# saha-aux.net
KiCad netlist of a schematic drawn in EAGLE
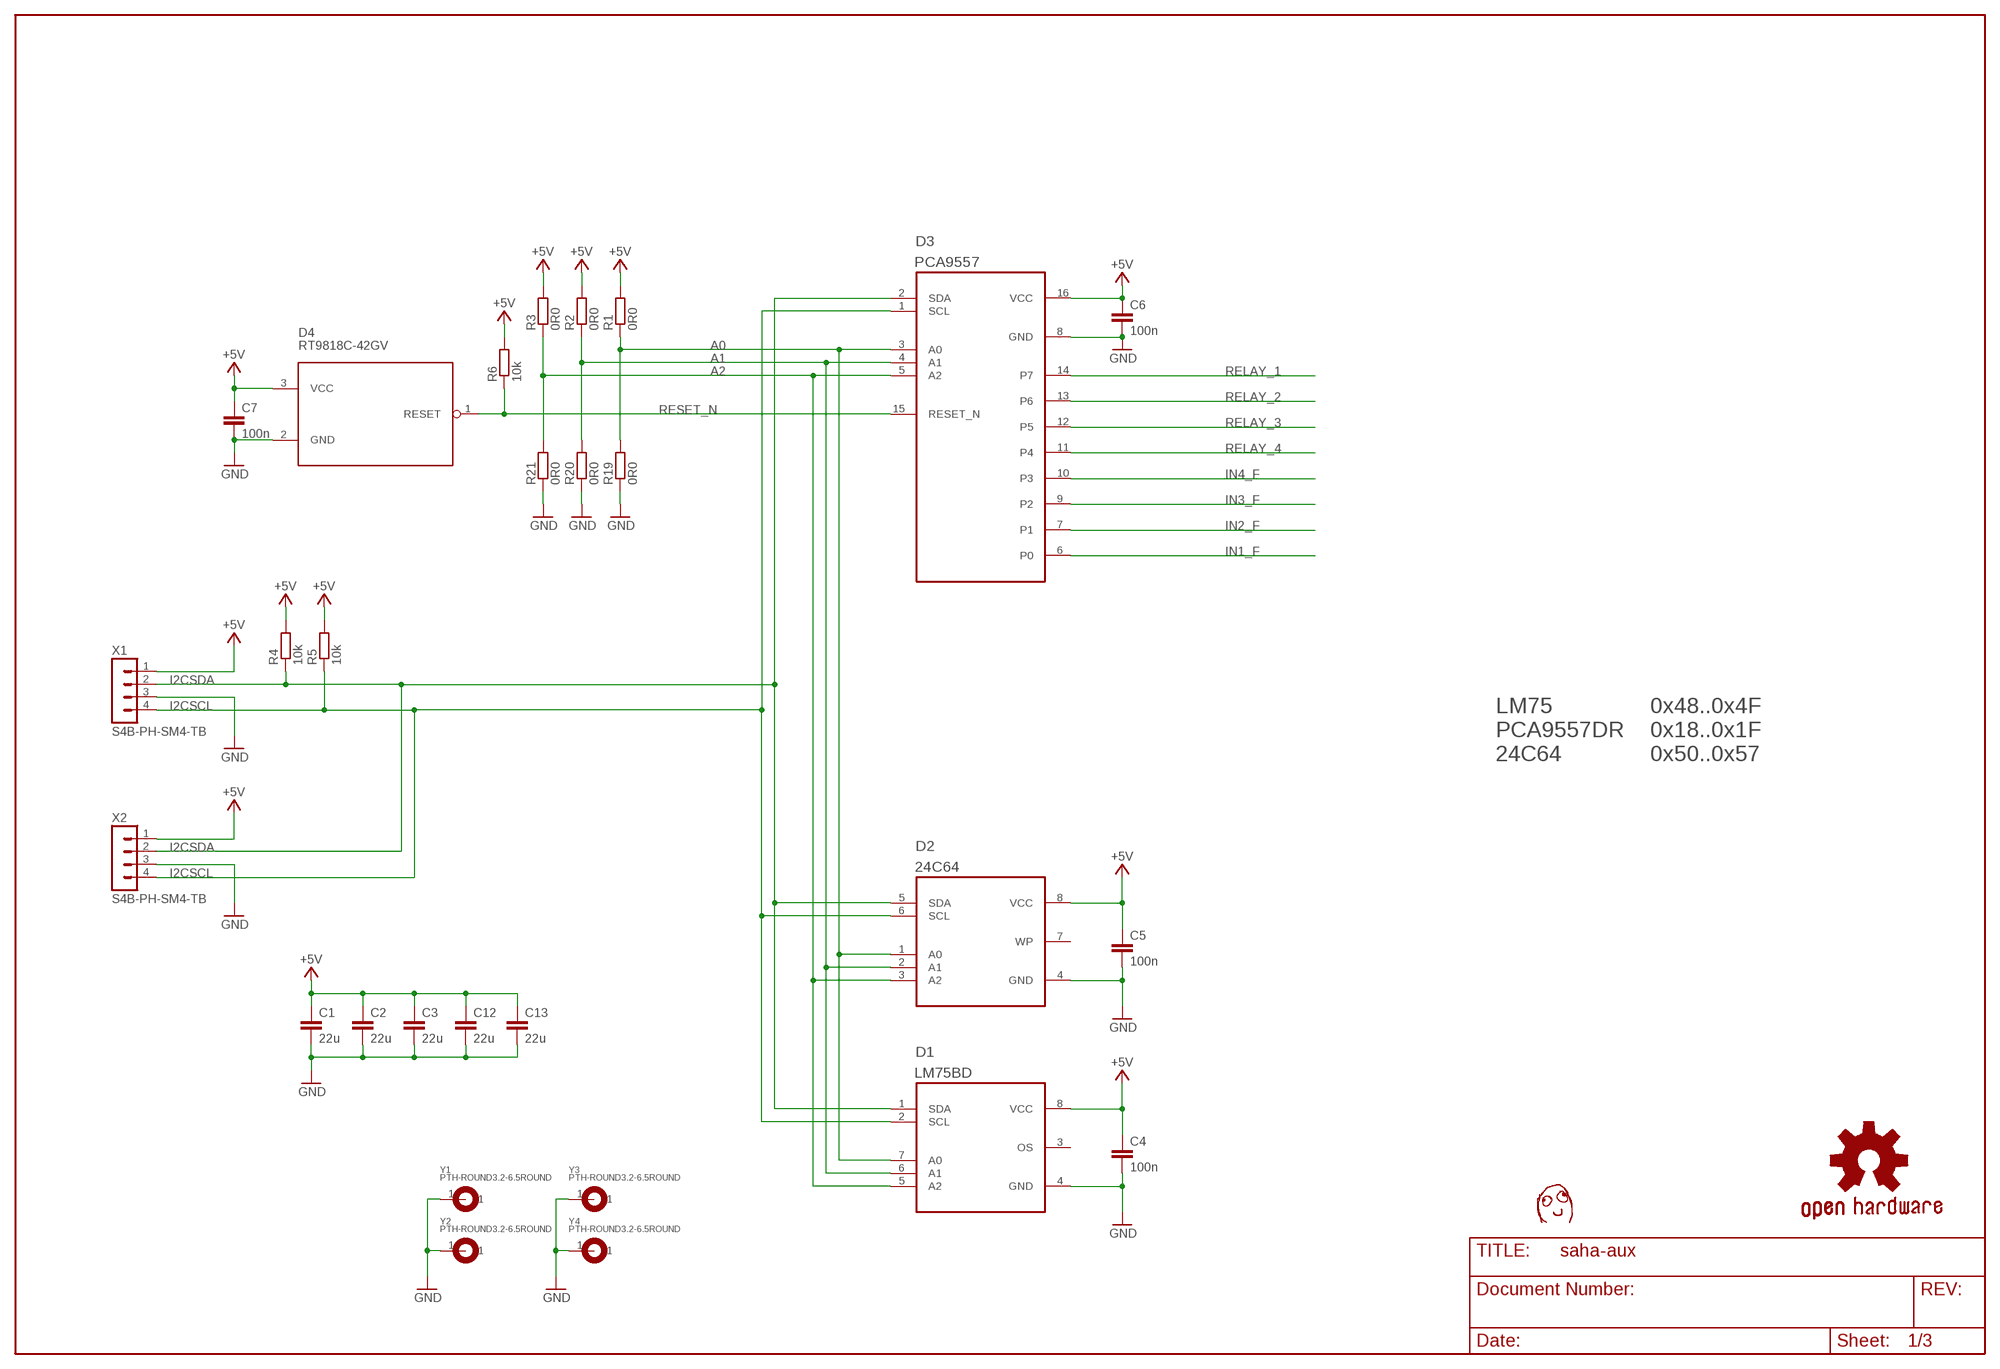
[diagram p0: schematic, sheet 1]
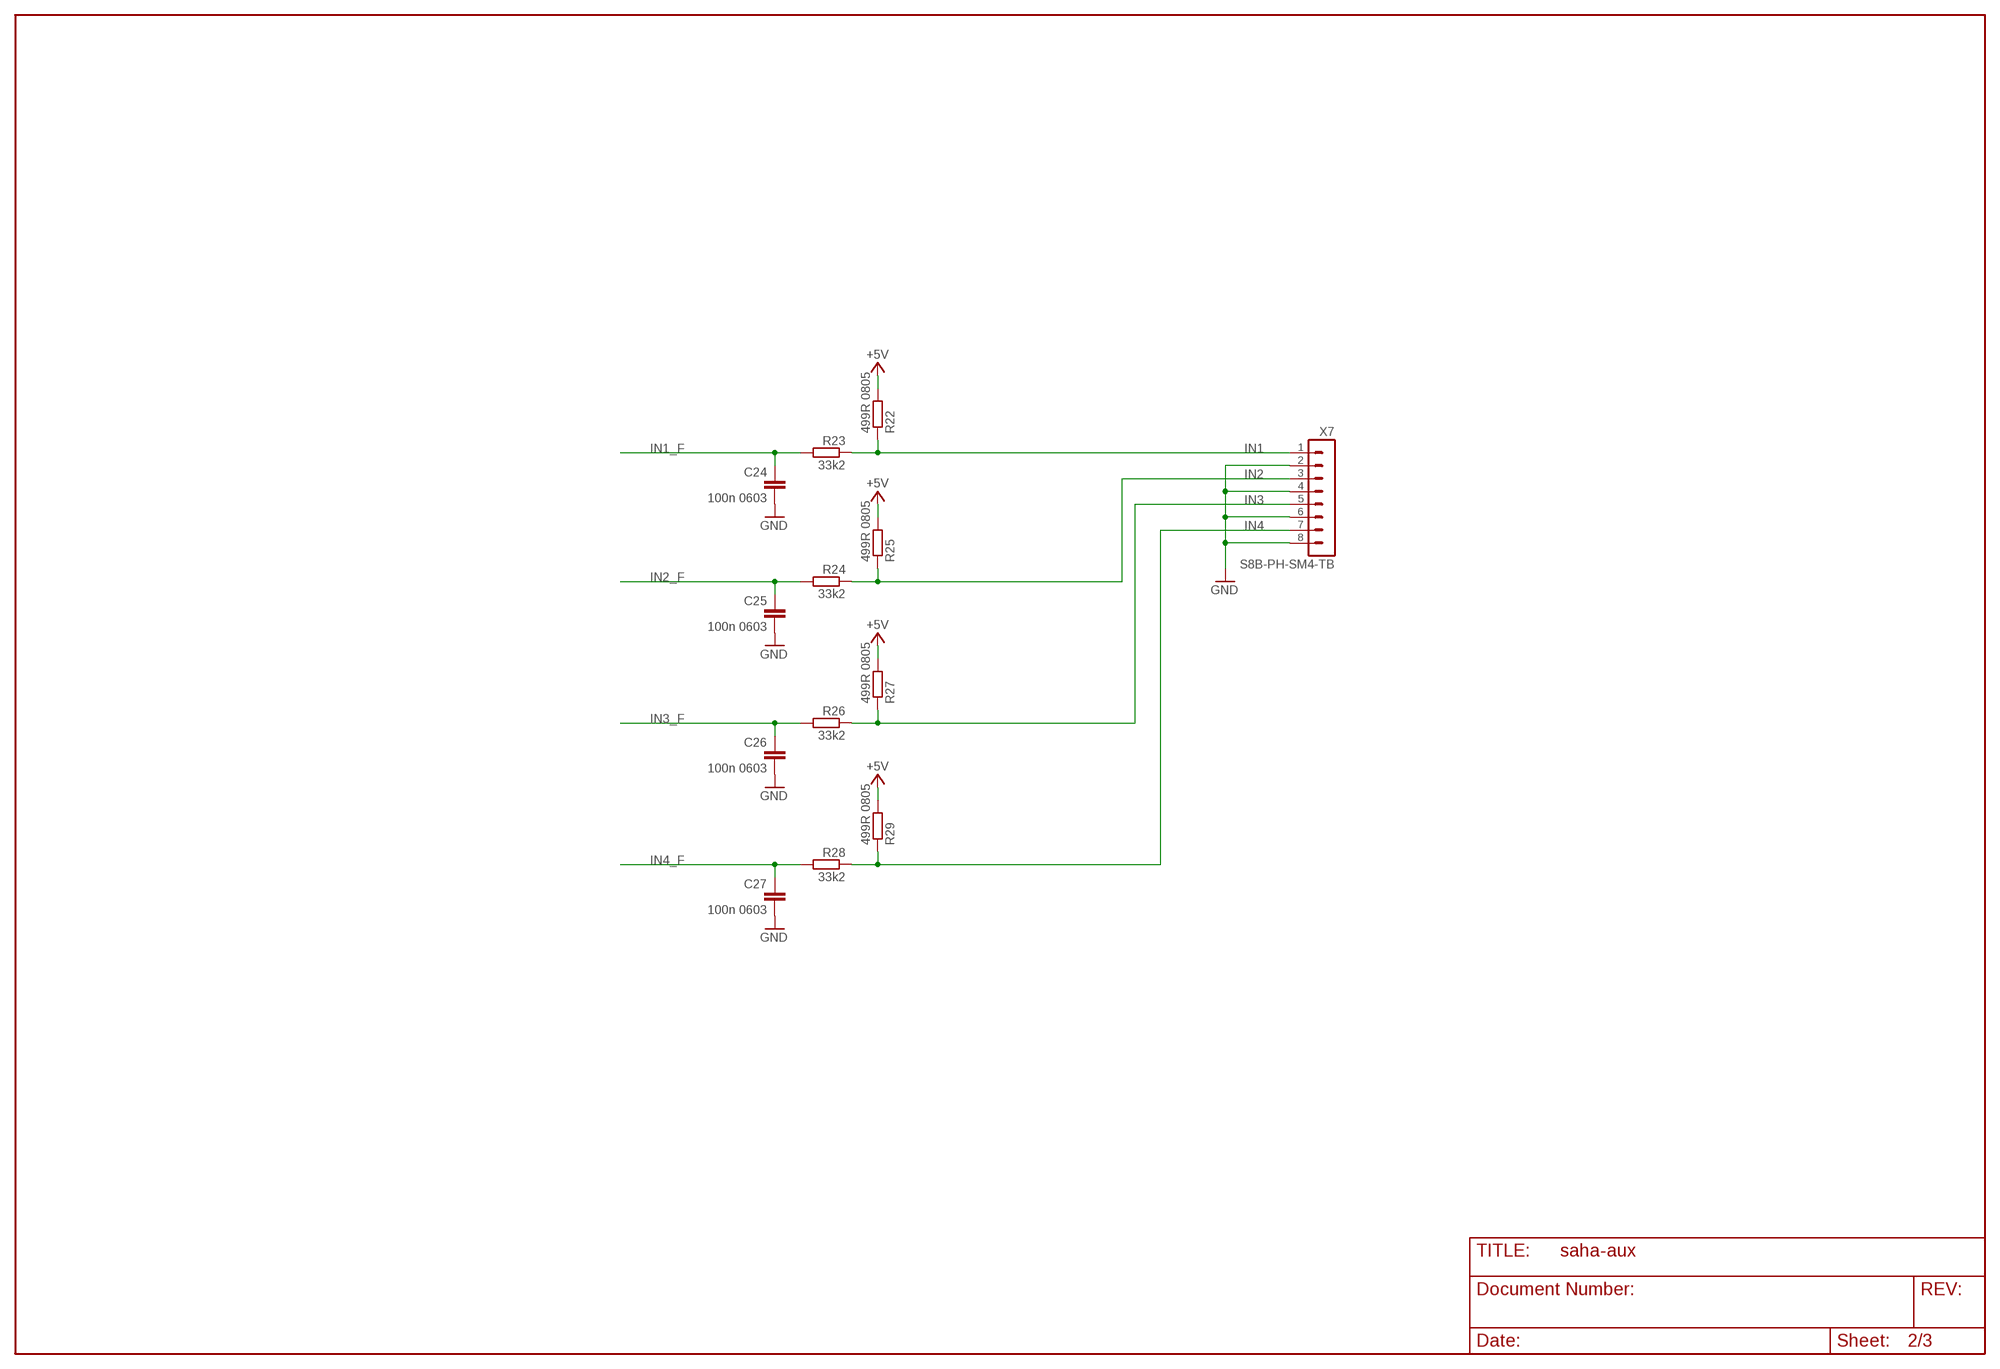
[diagram p1: schematic, sheet 2]
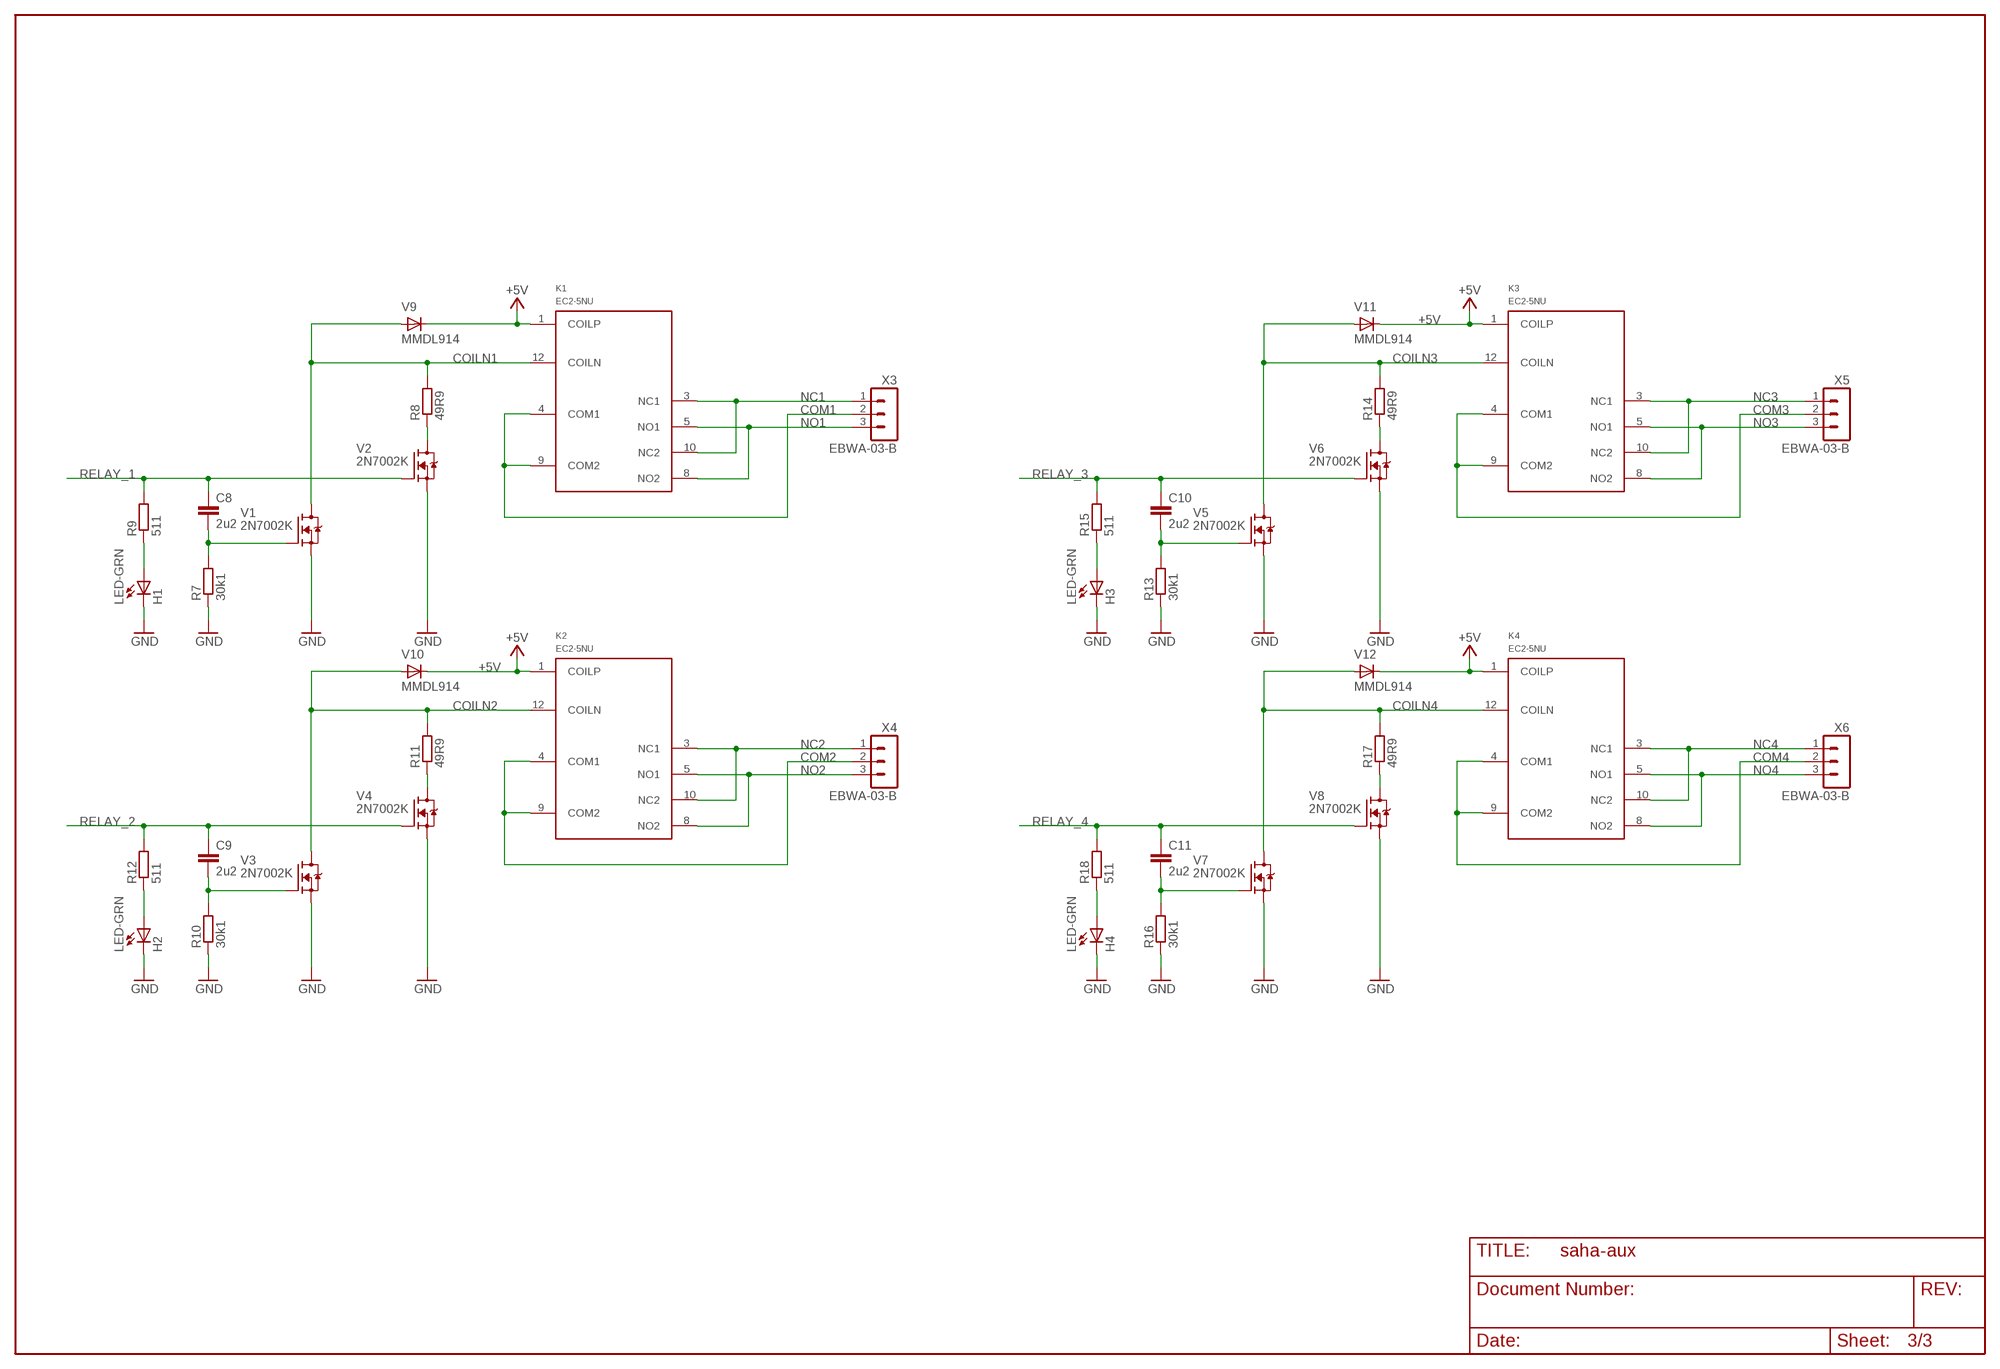
[diagram p2: schematic, sheet 3]

(export (version "E")
  (design (tool "Eeschema 10.0.6"))
  (components
    (comp (ref "C8")
      (value "2u2")
      (footprint "eagle-import:C0603")
      (libsource (lib "eagle-import") (part "CAP0603"))
    )
    (comp (ref "C9")
      (value "2u2")
      (footprint "eagle-import:C0603")
      (libsource (lib "eagle-import") (part "CAP0603"))
    )
    (comp (ref "C10")
      (value "2u2")
      (footprint "eagle-import:C0603")
      (libsource (lib "eagle-import") (part "CAP0603"))
    )
    (comp (ref "C11")
      (value "2u2")
      (footprint "eagle-import:C0603")
      (libsource (lib "eagle-import") (part "CAP0603"))
    )
    (comp (ref "H1")
      (value "LED-GRN")
      (footprint "eagle-import:CHIP-LED0603")
      (libsource (lib "eagle-import") (part "LED-GRN"))
    )
    (comp (ref "H2")
      (value "LED-GRN")
      (footprint "eagle-import:CHIP-LED0603")
      (libsource (lib "eagle-import") (part "LED-GRN"))
    )
    (comp (ref "H3")
      (value "LED-GRN")
      (footprint "eagle-import:CHIP-LED0603")
      (libsource (lib "eagle-import") (part "LED-GRN"))
    )
    (comp (ref "H4")
      (value "LED-GRN")
      (footprint "eagle-import:CHIP-LED0603")
      (libsource (lib "eagle-import") (part "LED-GRN"))
    )
    (comp (ref "K1")
      (value "EC2-5NU")
      (footprint "eagle-import:EC2")
      (libsource (lib "eagle-import") (part "EC2-5NU"))
    )
    (comp (ref "K2")
      (value "EC2-5NU")
      (footprint "eagle-import:EC2")
      (libsource (lib "eagle-import") (part "EC2-5NU"))
    )
    (comp (ref "K3")
      (value "EC2-5NU")
      (footprint "eagle-import:EC2")
      (libsource (lib "eagle-import") (part "EC2-5NU"))
    )
    (comp (ref "K4")
      (value "EC2-5NU")
      (footprint "eagle-import:EC2")
      (libsource (lib "eagle-import") (part "EC2-5NU"))
    )
    (comp (ref "R7")
      (value "30k1")
      (footprint "eagle-import:R0603")
      (libsource (lib "eagle-import") (part "RES0603"))
    )
    (comp (ref "R8")
      (value "49R9")
      (footprint "eagle-import:R0805")
      (libsource (lib "eagle-import") (part "RES0805"))
    )
    (comp (ref "R9")
      (value "511")
      (footprint "eagle-import:R0603")
      (libsource (lib "eagle-import") (part "RES0603"))
    )
    (comp (ref "R10")
      (value "30k1")
      (footprint "eagle-import:R0603")
      (libsource (lib "eagle-import") (part "RES0603"))
    )
    (comp (ref "R11")
      (value "49R9")
      (footprint "eagle-import:R0805")
      (libsource (lib "eagle-import") (part "RES0805"))
    )
    (comp (ref "R12")
      (value "511")
      (footprint "eagle-import:R0603")
      (libsource (lib "eagle-import") (part "RES0603"))
    )
    (comp (ref "R13")
      (value "30k1")
      (footprint "eagle-import:R0603")
      (libsource (lib "eagle-import") (part "RES0603"))
    )
    (comp (ref "R14")
      (value "49R9")
      (footprint "eagle-import:R0805")
      (libsource (lib "eagle-import") (part "RES0805"))
    )
    (comp (ref "R15")
      (value "511")
      (footprint "eagle-import:R0603")
      (libsource (lib "eagle-import") (part "RES0603"))
    )
    (comp (ref "R16")
      (value "30k1")
      (footprint "eagle-import:R0603")
      (libsource (lib "eagle-import") (part "RES0603"))
    )
    (comp (ref "R17")
      (value "49R9")
      (footprint "eagle-import:R0805")
      (libsource (lib "eagle-import") (part "RES0805"))
    )
    (comp (ref "R18")
      (value "511")
      (footprint "eagle-import:R0603")
      (libsource (lib "eagle-import") (part "RES0603"))
    )
    (comp (ref "V1")
      (value "2N7002K")
      (footprint "eagle-import:SOT23")
      (libsource (lib "eagle-import") (part "2N7002K"))
    )
    (comp (ref "V2")
      (value "2N7002K")
      (footprint "eagle-import:SOT23")
      (libsource (lib "eagle-import") (part "2N7002K"))
    )
    (comp (ref "V3")
      (value "2N7002K")
      (footprint "eagle-import:SOT23")
      (libsource (lib "eagle-import") (part "2N7002K"))
    )
    (comp (ref "V4")
      (value "2N7002K")
      (footprint "eagle-import:SOT23")
      (libsource (lib "eagle-import") (part "2N7002K"))
    )
    (comp (ref "V5")
      (value "2N7002K")
      (footprint "eagle-import:SOT23")
      (libsource (lib "eagle-import") (part "2N7002K"))
    )
    (comp (ref "V6")
      (value "2N7002K")
      (footprint "eagle-import:SOT23")
      (libsource (lib "eagle-import") (part "2N7002K"))
    )
    (comp (ref "V7")
      (value "2N7002K")
      (footprint "eagle-import:SOT23")
      (libsource (lib "eagle-import") (part "2N7002K"))
    )
    (comp (ref "V8")
      (value "2N7002K")
      (footprint "eagle-import:SOT23")
      (libsource (lib "eagle-import") (part "2N7002K"))
    )
    (comp (ref "V9")
      (value "MMDL914")
      (footprint "eagle-import:SOD-323")
      (libsource (lib "eagle-import") (part "MMDL914"))
    )
    (comp (ref "V10")
      (value "MMDL914")
      (footprint "eagle-import:SOD-323")
      (libsource (lib "eagle-import") (part "MMDL914"))
    )
    (comp (ref "V11")
      (value "MMDL914")
      (footprint "eagle-import:SOD-323")
      (libsource (lib "eagle-import") (part "MMDL914"))
    )
    (comp (ref "V12")
      (value "MMDL914")
      (footprint "eagle-import:SOD-323")
      (libsource (lib "eagle-import") (part "MMDL914"))
    )
    (comp (ref "X3")
      (value "EBWA-03-B")
      (footprint "eagle-import:RUUVILIITIN381-3")
      (libsource (lib "eagle-import") (part "EBWA-03-B"))
    )
    (comp (ref "X4")
      (value "EBWA-03-B")
      (footprint "eagle-import:RUUVILIITIN381-3")
      (libsource (lib "eagle-import") (part "EBWA-03-B"))
    )
    (comp (ref "X5")
      (value "EBWA-03-B")
      (footprint "eagle-import:RUUVILIITIN381-3")
      (libsource (lib "eagle-import") (part "EBWA-03-B"))
    )
    (comp (ref "X6")
      (value "EBWA-03-B")
      (footprint "eagle-import:RUUVILIITIN381-3")
      (libsource (lib "eagle-import") (part "EBWA-03-B"))
    )
    (comp (ref "C1")
      (value "22u")
      (footprint "eagle-import:C0805")
      (libsource (lib "eagle-import") (part "CAP0805"))
    )
    (comp (ref "C2")
      (value "22u")
      (footprint "eagle-import:C0805")
      (libsource (lib "eagle-import") (part "CAP0805"))
    )
    (comp (ref "C3")
      (value "22u")
      (footprint "eagle-import:C0805")
      (libsource (lib "eagle-import") (part "CAP0805"))
    )
    (comp (ref "C4")
      (value "100n")
      (footprint "eagle-import:C0603")
      (libsource (lib "eagle-import") (part "CAP0603"))
    )
    (comp (ref "C5")
      (value "100n")
      (footprint "eagle-import:C0603")
      (libsource (lib "eagle-import") (part "CAP0603"))
    )
    (comp (ref "C6")
      (value "100n")
      (footprint "eagle-import:C0603")
      (libsource (lib "eagle-import") (part "CAP0603"))
    )
    (comp (ref "C7")
      (value "100n")
      (footprint "eagle-import:C0603")
      (libsource (lib "eagle-import") (part "CAP0603"))
    )
    (comp (ref "C12")
      (value "22u")
      (footprint "eagle-import:C0805")
      (libsource (lib "eagle-import") (part "CAP0805"))
    )
    (comp (ref "C13")
      (value "22u")
      (footprint "eagle-import:C0805")
      (libsource (lib "eagle-import") (part "CAP0805"))
    )
    (comp (ref "D1")
      (value "LM75BD")
      (footprint "eagle-import:SOIC8-N")
      (libsource (lib "eagle-import") (part "LM75BD"))
    )
    (comp (ref "D2")
      (value "24C64")
      (footprint "eagle-import:SOIC8-N")
      (libsource (lib "eagle-import") (part "24C64"))
    )
    (comp (ref "D3")
      (value "PCA9557")
      (footprint "eagle-import:SOIC16-N")
      (libsource (lib "eagle-import") (part "PCA9557"))
    )
    (comp (ref "D4")
      (value "RT9818C-42GV")
      (footprint "eagle-import:SOT23")
      (libsource (lib "eagle-import") (part "RT9818C-42GV"))
    )
    (comp (ref "R1")
      (value "0R0")
      (footprint "eagle-import:R0603")
      (libsource (lib "eagle-import") (part "RES0603"))
    )
    (comp (ref "R2")
      (value "0R0")
      (footprint "eagle-import:R0603")
      (libsource (lib "eagle-import") (part "RES0603"))
    )
    (comp (ref "R3")
      (value "0R0")
      (footprint "eagle-import:R0603")
      (libsource (lib "eagle-import") (part "RES0603"))
    )
    (comp (ref "R4")
      (value "10k")
      (footprint "eagle-import:R0603")
      (libsource (lib "eagle-import") (part "RES0603"))
    )
    (comp (ref "R5")
      (value "10k")
      (footprint "eagle-import:R0603")
      (libsource (lib "eagle-import") (part "RES0603"))
    )
    (comp (ref "R6")
      (value "10k")
      (footprint "eagle-import:R0603")
      (libsource (lib "eagle-import") (part "RES0603"))
    )
    (comp (ref "R19")
      (value "0R0")
      (footprint "eagle-import:R0603")
      (libsource (lib "eagle-import") (part "RES0603"))
    )
    (comp (ref "R20")
      (value "0R0")
      (footprint "eagle-import:R0603")
      (libsource (lib "eagle-import") (part "RES0603"))
    )
    (comp (ref "R21")
      (value "0R0")
      (footprint "eagle-import:R0603")
      (libsource (lib "eagle-import") (part "RES0603"))
    )
    (comp (ref "U$1")
      (value "DAFUG")
      (footprint "eagle-import:DAFUG")
      (libsource (lib "eagle-import") (part "DAFUG"))
    )
    (comp (ref "X1")
      (value "S4B-PH-SM4-TB")
      (footprint "eagle-import:JST-PH2.0-RA-4")
      (libsource (lib "eagle-import") (part "S4B-PH-SM4-TB"))
    )
    (comp (ref "X2")
      (value "S4B-PH-SM4-TB")
      (footprint "eagle-import:JST-PH2.0-RA-4")
      (libsource (lib "eagle-import") (part "S4B-PH-SM4-TB"))
    )
    (comp (ref "Y1")
      (value "PTH-ROUND3.2-6.5ROUND")
      (footprint "eagle-import:EKE_PTH-3.2-6.5")
      (libsource (lib "eagle-import") (part "PTH-ROUND3.2-6.5ROUND"))
    )
    (comp (ref "Y2")
      (value "PTH-ROUND3.2-6.5ROUND")
      (footprint "eagle-import:EKE_PTH-3.2-6.5")
      (libsource (lib "eagle-import") (part "PTH-ROUND3.2-6.5ROUND"))
    )
    (comp (ref "Y3")
      (value "PTH-ROUND3.2-6.5ROUND")
      (footprint "eagle-import:EKE_PTH-3.2-6.5")
      (libsource (lib "eagle-import") (part "PTH-ROUND3.2-6.5ROUND"))
    )
    (comp (ref "Y4")
      (value "PTH-ROUND3.2-6.5ROUND")
      (footprint "eagle-import:EKE_PTH-3.2-6.5")
      (libsource (lib "eagle-import") (part "PTH-ROUND3.2-6.5ROUND"))
    )
    (comp (ref "C24")
      (value "100n 0603")
      (footprint "eagle-import:C0603")
      (libsource (lib "eagle-import") (part "saha-cpu_CAP0603"))
    )
    (comp (ref "C25")
      (value "100n 0603")
      (footprint "eagle-import:C0603")
      (libsource (lib "eagle-import") (part "saha-cpu_CAP0603"))
    )
    (comp (ref "C26")
      (value "100n 0603")
      (footprint "eagle-import:C0603")
      (libsource (lib "eagle-import") (part "saha-cpu_CAP0603"))
    )
    (comp (ref "C27")
      (value "100n 0603")
      (footprint "eagle-import:C0603")
      (libsource (lib "eagle-import") (part "saha-cpu_CAP0603"))
    )
    (comp (ref "R22")
      (value "499R 0805")
      (footprint "eagle-import:R0805")
      (libsource (lib "eagle-import") (part "saha-cpu_RES0805"))
    )
    (comp (ref "R23")
      (value "33k2")
      (footprint "eagle-import:R0603")
      (libsource (lib "eagle-import") (part "saha-cpu_RES0603"))
    )
    (comp (ref "R24")
      (value "33k2")
      (footprint "eagle-import:R0603")
      (libsource (lib "eagle-import") (part "saha-cpu_RES0603"))
    )
    (comp (ref "R25")
      (value "499R 0805")
      (footprint "eagle-import:R0805")
      (libsource (lib "eagle-import") (part "saha-cpu_RES0805"))
    )
    (comp (ref "R26")
      (value "33k2")
      (footprint "eagle-import:R0603")
      (libsource (lib "eagle-import") (part "saha-cpu_RES0603"))
    )
    (comp (ref "R27")
      (value "499R 0805")
      (footprint "eagle-import:R0805")
      (libsource (lib "eagle-import") (part "saha-cpu_RES0805"))
    )
    (comp (ref "R28")
      (value "33k2")
      (footprint "eagle-import:R0603")
      (libsource (lib "eagle-import") (part "saha-cpu_RES0603"))
    )
    (comp (ref "R29")
      (value "499R 0805")
      (footprint "eagle-import:R0805")
      (libsource (lib "eagle-import") (part "saha-cpu_RES0805"))
    )
    (comp (ref "X7")
      (value "S8B-PH-SM4-TB")
      (footprint "eagle-import:JST-PH2.0-RA-8")
      (libsource (lib "eagle-import") (part "S8B-PH-SM4-TB"))
    )
  )
  (nets
    (net (code "1") (name "+5V") (class "Default")
      (node (ref "C1") (pin "1") (pinfunction "1_1") (pintype "passive"))
      (node (ref "C12") (pin "1") (pinfunction "1_1") (pintype "passive"))
      (node (ref "C13") (pin "1") (pinfunction "1_1") (pintype "passive"))
      (node (ref "C2") (pin "1") (pinfunction "1_1") (pintype "passive"))
      (node (ref "C3") (pin "1") (pinfunction "1_1") (pintype "passive"))
      (node (ref "C4") (pin "1") (pinfunction "1_1") (pintype "passive"))
      (node (ref "C5") (pin "1") (pinfunction "1_1") (pintype "passive"))
      (node (ref "C6") (pin "1") (pinfunction "1_1") (pintype "passive"))
      (node (ref "C7") (pin "1") (pinfunction "1_1") (pintype "passive"))
      (node (ref "D1") (pin "8") (pinfunction "VCC_8") (pintype "bidirectional"))
      (node (ref "D2") (pin "8") (pinfunction "VCC_8") (pintype "bidirectional"))
      (node (ref "D3") (pin "16") (pinfunction "VCC_16") (pintype "bidirectional"))
      (node (ref "D4") (pin "3") (pinfunction "VCC_3") (pintype "bidirectional"))
      (node (ref "K1") (pin "1") (pinfunction "COILP_1") (pintype "bidirectional"))
      (node (ref "K2") (pin "1") (pinfunction "COILP_1") (pintype "bidirectional"))
      (node (ref "K3") (pin "1") (pinfunction "COILP_1") (pintype "bidirectional"))
      (node (ref "K4") (pin "1") (pinfunction "COILP_1") (pintype "bidirectional"))
      (node (ref "R1") (pin "2") (pinfunction "2_2") (pintype "passive"))
      (node (ref "R2") (pin "2") (pinfunction "2_2") (pintype "passive"))
      (node (ref "R22") (pin "2") (pinfunction "2_2") (pintype "passive"))
      (node (ref "R25") (pin "2") (pinfunction "2_2") (pintype "passive"))
      (node (ref "R27") (pin "2") (pinfunction "2_2") (pintype "passive"))
      (node (ref "R29") (pin "2") (pinfunction "2_2") (pintype "passive"))
      (node (ref "R3") (pin "2") (pinfunction "2_2") (pintype "passive"))
      (node (ref "R4") (pin "2") (pinfunction "2_2") (pintype "passive"))
      (node (ref "R5") (pin "2") (pinfunction "2_2") (pintype "passive"))
      (node (ref "R6") (pin "2") (pinfunction "2_2") (pintype "passive"))
      (node (ref "V10") (pin "C") (pinfunction "C_C") (pintype "passive"))
      (node (ref "V11") (pin "C") (pinfunction "C_C") (pintype "passive"))
      (node (ref "V12") (pin "C") (pinfunction "C_C") (pintype "passive"))
      (node (ref "V9") (pin "C") (pinfunction "C_C") (pintype "passive"))
      (node (ref "X1") (pin "1") (pinfunction "1_1") (pintype "passive"))
      (node (ref "X2") (pin "1") (pinfunction "1_1") (pintype "passive"))
    )
    (net (code "2") (name "A0") (class "Default")
      (node (ref "D1") (pin "7") (pinfunction "A0_7") (pintype "bidirectional"))
      (node (ref "D2") (pin "1") (pinfunction "A0_1") (pintype "bidirectional"))
      (node (ref "D3") (pin "3") (pinfunction "A0_3") (pintype "bidirectional"))
      (node (ref "R1") (pin "1") (pinfunction "1_1") (pintype "passive"))
      (node (ref "R19") (pin "2") (pinfunction "2_2") (pintype "passive"))
    )
    (net (code "3") (name "A1") (class "Default")
      (node (ref "D1") (pin "6") (pinfunction "A1_6") (pintype "bidirectional"))
      (node (ref "D2") (pin "2") (pinfunction "A1_2") (pintype "bidirectional"))
      (node (ref "D3") (pin "4") (pinfunction "A1_4") (pintype "bidirectional"))
      (node (ref "R2") (pin "1") (pinfunction "1_1") (pintype "passive"))
      (node (ref "R20") (pin "2") (pinfunction "2_2") (pintype "passive"))
    )
    (net (code "4") (name "A2") (class "Default")
      (node (ref "D1") (pin "5") (pinfunction "A2_5") (pintype "bidirectional"))
      (node (ref "D2") (pin "3") (pinfunction "A2_3") (pintype "bidirectional"))
      (node (ref "D3") (pin "5") (pinfunction "A2_5") (pintype "bidirectional"))
      (node (ref "R21") (pin "2") (pinfunction "2_2") (pintype "passive"))
      (node (ref "R3") (pin "1") (pinfunction "1_1") (pintype "passive"))
    )
    (net (code "5") (name "COILN1") (class "Default")
      (node (ref "K1") (pin "12") (pinfunction "COILN_12") (pintype "bidirectional"))
      (node (ref "R8") (pin "2") (pinfunction "2_2") (pintype "passive"))
      (node (ref "V1") (pin "3") (pinfunction "D_3") (pintype "passive"))
      (node (ref "V9") (pin "A") (pinfunction "A_A") (pintype "passive"))
    )
    (net (code "6") (name "COILN2") (class "Default")
      (node (ref "K2") (pin "12") (pinfunction "COILN_12") (pintype "bidirectional"))
      (node (ref "R11") (pin "2") (pinfunction "2_2") (pintype "passive"))
      (node (ref "V10") (pin "A") (pinfunction "A_A") (pintype "passive"))
      (node (ref "V3") (pin "3") (pinfunction "D_3") (pintype "passive"))
    )
    (net (code "7") (name "COILN3") (class "Default")
      (node (ref "K3") (pin "12") (pinfunction "COILN_12") (pintype "bidirectional"))
      (node (ref "R14") (pin "2") (pinfunction "2_2") (pintype "passive"))
      (node (ref "V11") (pin "A") (pinfunction "A_A") (pintype "passive"))
      (node (ref "V5") (pin "3") (pinfunction "D_3") (pintype "passive"))
    )
    (net (code "8") (name "COILN4") (class "Default")
      (node (ref "K4") (pin "12") (pinfunction "COILN_12") (pintype "bidirectional"))
      (node (ref "R17") (pin "2") (pinfunction "2_2") (pintype "passive"))
      (node (ref "V12") (pin "A") (pinfunction "A_A") (pintype "passive"))
      (node (ref "V7") (pin "3") (pinfunction "D_3") (pintype "passive"))
    )
    (net (code "9") (name "COM1") (class "Default")
      (node (ref "K1") (pin "4") (pinfunction "COM1_4") (pintype "bidirectional"))
      (node (ref "K1") (pin "9") (pinfunction "COM2_9") (pintype "bidirectional"))
      (node (ref "X3") (pin "2") (pinfunction "2_2") (pintype "passive"))
    )
    (net (code "10") (name "COM2") (class "Default")
      (node (ref "K2") (pin "4") (pinfunction "COM1_4") (pintype "bidirectional"))
      (node (ref "K2") (pin "9") (pinfunction "COM2_9") (pintype "bidirectional"))
      (node (ref "X4") (pin "2") (pinfunction "2_2") (pintype "passive"))
    )
    (net (code "11") (name "COM3") (class "Default")
      (node (ref "K3") (pin "4") (pinfunction "COM1_4") (pintype "bidirectional"))
      (node (ref "K3") (pin "9") (pinfunction "COM2_9") (pintype "bidirectional"))
      (node (ref "X5") (pin "2") (pinfunction "2_2") (pintype "passive"))
    )
    (net (code "12") (name "COM4") (class "Default")
      (node (ref "K4") (pin "4") (pinfunction "COM1_4") (pintype "bidirectional"))
      (node (ref "K4") (pin "9") (pinfunction "COM2_9") (pintype "bidirectional"))
      (node (ref "X6") (pin "2") (pinfunction "2_2") (pintype "passive"))
    )
    (net (code "13") (name "GND") (class "Default")
      (node (ref "C1") (pin "2") (pinfunction "2_2") (pintype "passive"))
      (node (ref "C12") (pin "2") (pinfunction "2_2") (pintype "passive"))
      (node (ref "C13") (pin "2") (pinfunction "2_2") (pintype "passive"))
      (node (ref "C2") (pin "2") (pinfunction "2_2") (pintype "passive"))
      (node (ref "C24") (pin "2") (pinfunction "2_2") (pintype "passive"))
      (node (ref "C25") (pin "2") (pinfunction "2_2") (pintype "passive"))
      (node (ref "C26") (pin "2") (pinfunction "2_2") (pintype "passive"))
      (node (ref "C27") (pin "2") (pinfunction "2_2") (pintype "passive"))
      (node (ref "C3") (pin "2") (pinfunction "2_2") (pintype "passive"))
      (node (ref "C4") (pin "2") (pinfunction "2_2") (pintype "passive"))
      (node (ref "C5") (pin "2") (pinfunction "2_2") (pintype "passive"))
      (node (ref "C6") (pin "2") (pinfunction "2_2") (pintype "passive"))
      (node (ref "C7") (pin "2") (pinfunction "2_2") (pintype "passive"))
      (node (ref "D1") (pin "4") (pinfunction "GND_4") (pintype "input"))
      (node (ref "D2") (pin "4") (pinfunction "GND_4") (pintype "input"))
      (node (ref "D3") (pin "8") (pinfunction "GND_8") (pintype "bidirectional"))
      (node (ref "D4") (pin "2") (pinfunction "GND_2") (pintype "bidirectional"))
      (node (ref "H1") (pin "C") (pinfunction "C_C") (pintype "passive"))
      (node (ref "H2") (pin "C") (pinfunction "C_C") (pintype "passive"))
      (node (ref "H3") (pin "C") (pinfunction "C_C") (pintype "passive"))
      (node (ref "H4") (pin "C") (pinfunction "C_C") (pintype "passive"))
      (node (ref "R10") (pin "1") (pinfunction "1_1") (pintype "passive"))
      (node (ref "R13") (pin "1") (pinfunction "1_1") (pintype "passive"))
      (node (ref "R16") (pin "1") (pinfunction "1_1") (pintype "passive"))
      (node (ref "R19") (pin "1") (pinfunction "1_1") (pintype "passive"))
      (node (ref "R20") (pin "1") (pinfunction "1_1") (pintype "passive"))
      (node (ref "R21") (pin "1") (pinfunction "1_1") (pintype "passive"))
      (node (ref "R7") (pin "1") (pinfunction "1_1") (pintype "passive"))
      (node (ref "V1") (pin "2") (pinfunction "S_2") (pintype "passive"))
      (node (ref "V2") (pin "2") (pinfunction "S_2") (pintype "passive"))
      (node (ref "V3") (pin "2") (pinfunction "S_2") (pintype "passive"))
      (node (ref "V4") (pin "2") (pinfunction "S_2") (pintype "passive"))
      (node (ref "V5") (pin "2") (pinfunction "S_2") (pintype "passive"))
      (node (ref "V6") (pin "2") (pinfunction "S_2") (pintype "passive"))
      (node (ref "V7") (pin "2") (pinfunction "S_2") (pintype "passive"))
      (node (ref "V8") (pin "2") (pinfunction "S_2") (pintype "passive"))
      (node (ref "X1") (pin "3") (pinfunction "3_3") (pintype "passive"))
      (node (ref "X2") (pin "3") (pinfunction "3_3") (pintype "passive"))
      (node (ref "X7") (pin "2") (pinfunction "2_2") (pintype "passive"))
      (node (ref "X7") (pin "4") (pinfunction "4_4") (pintype "passive"))
      (node (ref "X7") (pin "6") (pinfunction "6_6") (pintype "passive"))
      (node (ref "X7") (pin "8") (pinfunction "8_8") (pintype "passive"))
      (node (ref "Y1") (pin "1") (pinfunction "1_1") (pintype "bidirectional"))
      (node (ref "Y2") (pin "1") (pinfunction "1_1") (pintype "bidirectional"))
      (node (ref "Y3") (pin "1") (pinfunction "1_1") (pintype "bidirectional"))
      (node (ref "Y4") (pin "1") (pinfunction "1_1") (pintype "bidirectional"))
    )
    (net (code "14") (name "I2CSCL") (class "Default")
      (node (ref "D1") (pin "2") (pinfunction "SCL_2") (pintype "bidirectional"))
      (node (ref "D2") (pin "6") (pinfunction "SCL_6") (pintype "bidirectional"))
      (node (ref "D3") (pin "1") (pinfunction "SCL_1") (pintype "bidirectional"))
      (node (ref "R5") (pin "1") (pinfunction "1_1") (pintype "passive"))
      (node (ref "X1") (pin "4") (pinfunction "4_4") (pintype "passive"))
      (node (ref "X2") (pin "4") (pinfunction "4_4") (pintype "passive"))
    )
    (net (code "15") (name "I2CSDA") (class "Default")
      (node (ref "D1") (pin "1") (pinfunction "SDA_1") (pintype "power_in"))
      (node (ref "D2") (pin "5") (pinfunction "SDA_5") (pintype "power_in"))
      (node (ref "D3") (pin "2") (pinfunction "SDA_2") (pintype "power_in"))
      (node (ref "R4") (pin "1") (pinfunction "1_1") (pintype "passive"))
      (node (ref "X1") (pin "2") (pinfunction "2_2") (pintype "passive"))
      (node (ref "X2") (pin "2") (pinfunction "2_2") (pintype "passive"))
    )
    (net (code "16") (name "IN1") (class "Default")
      (node (ref "R22") (pin "1") (pinfunction "1_1") (pintype "passive"))
      (node (ref "R23") (pin "1") (pinfunction "1_1") (pintype "passive"))
      (node (ref "X7") (pin "1") (pinfunction "1_1") (pintype "passive"))
    )
    (net (code "17") (name "IN1_F") (class "Default")
      (node (ref "C24") (pin "1") (pinfunction "1_1") (pintype "passive"))
      (node (ref "D3") (pin "6") (pinfunction "P0_6") (pintype "input"))
      (node (ref "R23") (pin "2") (pinfunction "2_2") (pintype "passive"))
    )
    (net (code "18") (name "IN2") (class "Default")
      (node (ref "R24") (pin "1") (pinfunction "1_1") (pintype "passive"))
      (node (ref "R25") (pin "1") (pinfunction "1_1") (pintype "passive"))
      (node (ref "X7") (pin "3") (pinfunction "3_3") (pintype "passive"))
    )
    (net (code "19") (name "IN2_F") (class "Default")
      (node (ref "C25") (pin "1") (pinfunction "1_1") (pintype "passive"))
      (node (ref "D3") (pin "7") (pinfunction "P1_7") (pintype "input"))
      (node (ref "R24") (pin "2") (pinfunction "2_2") (pintype "passive"))
    )
    (net (code "20") (name "IN3") (class "Default")
      (node (ref "R26") (pin "1") (pinfunction "1_1") (pintype "passive"))
      (node (ref "R27") (pin "1") (pinfunction "1_1") (pintype "passive"))
      (node (ref "X7") (pin "5") (pinfunction "5_5") (pintype "passive"))
    )
    (net (code "21") (name "IN3_F") (class "Default")
      (node (ref "C26") (pin "1") (pinfunction "1_1") (pintype "passive"))
      (node (ref "D3") (pin "9") (pinfunction "P2_9") (pintype "input"))
      (node (ref "R26") (pin "2") (pinfunction "2_2") (pintype "passive"))
    )
    (net (code "22") (name "IN4") (class "Default")
      (node (ref "R28") (pin "1") (pinfunction "1_1") (pintype "passive"))
      (node (ref "R29") (pin "1") (pinfunction "1_1") (pintype "passive"))
      (node (ref "X7") (pin "7") (pinfunction "7_7") (pintype "passive"))
    )
    (net (code "23") (name "IN4_F") (class "Default")
      (node (ref "C27") (pin "1") (pinfunction "1_1") (pintype "passive"))
      (node (ref "D3") (pin "10") (pinfunction "P3_10") (pintype "input"))
      (node (ref "R28") (pin "2") (pinfunction "2_2") (pintype "passive"))
    )
    (net (code "24") (name "NC1") (class "Default")
      (node (ref "K1") (pin "10") (pinfunction "NC2_10") (pintype "bidirectional"))
      (node (ref "K1") (pin "3") (pinfunction "NC1_3") (pintype "bidirectional"))
      (node (ref "X3") (pin "1") (pinfunction "1_1") (pintype "passive"))
    )
    (net (code "25") (name "NC2") (class "Default")
      (node (ref "K2") (pin "10") (pinfunction "NC2_10") (pintype "bidirectional"))
      (node (ref "K2") (pin "3") (pinfunction "NC1_3") (pintype "bidirectional"))
      (node (ref "X4") (pin "1") (pinfunction "1_1") (pintype "passive"))
    )
    (net (code "26") (name "NC3") (class "Default")
      (node (ref "K3") (pin "10") (pinfunction "NC2_10") (pintype "bidirectional"))
      (node (ref "K3") (pin "3") (pinfunction "NC1_3") (pintype "bidirectional"))
      (node (ref "X5") (pin "1") (pinfunction "1_1") (pintype "passive"))
    )
    (net (code "27") (name "NC4") (class "Default")
      (node (ref "K4") (pin "10") (pinfunction "NC2_10") (pintype "bidirectional"))
      (node (ref "K4") (pin "3") (pinfunction "NC1_3") (pintype "bidirectional"))
      (node (ref "X6") (pin "1") (pinfunction "1_1") (pintype "passive"))
    )
    (net (code "28") (name "NO1") (class "Default")
      (node (ref "K1") (pin "5") (pinfunction "NO1_5") (pintype "bidirectional"))
      (node (ref "K1") (pin "8") (pinfunction "NO2_8") (pintype "bidirectional"))
      (node (ref "X3") (pin "3") (pinfunction "3_3") (pintype "passive"))
    )
    (net (code "29") (name "NO2") (class "Default")
      (node (ref "K2") (pin "5") (pinfunction "NO1_5") (pintype "bidirectional"))
      (node (ref "K2") (pin "8") (pinfunction "NO2_8") (pintype "bidirectional"))
      (node (ref "X4") (pin "3") (pinfunction "3_3") (pintype "passive"))
    )
    (net (code "30") (name "NO3") (class "Default")
      (node (ref "K3") (pin "5") (pinfunction "NO1_5") (pintype "bidirectional"))
      (node (ref "K3") (pin "8") (pinfunction "NO2_8") (pintype "bidirectional"))
      (node (ref "X5") (pin "3") (pinfunction "3_3") (pintype "passive"))
    )
    (net (code "31") (name "NO4") (class "Default")
      (node (ref "K4") (pin "5") (pinfunction "NO1_5") (pintype "bidirectional"))
      (node (ref "K4") (pin "8") (pinfunction "NO2_8") (pintype "bidirectional"))
      (node (ref "X6") (pin "3") (pinfunction "3_3") (pintype "passive"))
    )
    (net (code "32") (name "Net-(H1-PadA)") (class "Default")
      (node (ref "H1") (pin "A") (pinfunction "A_A") (pintype "passive"))
      (node (ref "R9") (pin "1") (pinfunction "1_1") (pintype "passive"))
    )
    (net (code "33") (name "Net-(H2-PadA)") (class "Default")
      (node (ref "H2") (pin "A") (pinfunction "A_A") (pintype "passive"))
      (node (ref "R12") (pin "1") (pinfunction "1_1") (pintype "passive"))
    )
    (net (code "34") (name "Net-(H3-PadA)") (class "Default")
      (node (ref "H3") (pin "A") (pinfunction "A_A") (pintype "passive"))
      (node (ref "R15") (pin "1") (pinfunction "1_1") (pintype "passive"))
    )
    (net (code "35") (name "Net-(H4-PadA)") (class "Default")
      (node (ref "H4") (pin "A") (pinfunction "A_A") (pintype "passive"))
      (node (ref "R18") (pin "1") (pinfunction "1_1") (pintype "passive"))
    )
    (net (code "36") (name "Net-(V1-G)") (class "Default")
      (node (ref "C8") (pin "2") (pinfunction "2_2") (pintype "passive"))
      (node (ref "R7") (pin "2") (pinfunction "2_2") (pintype "passive"))
      (node (ref "V1") (pin "1") (pinfunction "G_1") (pintype "passive"))
    )
    (net (code "37") (name "Net-(V2-D)") (class "Default")
      (node (ref "R8") (pin "1") (pinfunction "1_1") (pintype "passive"))
      (node (ref "V2") (pin "3") (pinfunction "D_3") (pintype "passive"))
    )
    (net (code "38") (name "Net-(V3-G)") (class "Default")
      (node (ref "C9") (pin "2") (pinfunction "2_2") (pintype "passive"))
      (node (ref "R10") (pin "2") (pinfunction "2_2") (pintype "passive"))
      (node (ref "V3") (pin "1") (pinfunction "G_1") (pintype "passive"))
    )
    (net (code "39") (name "Net-(V4-D)") (class "Default")
      (node (ref "R11") (pin "1") (pinfunction "1_1") (pintype "passive"))
      (node (ref "V4") (pin "3") (pinfunction "D_3") (pintype "passive"))
    )
    (net (code "40") (name "Net-(V5-G)") (class "Default")
      (node (ref "C10") (pin "2") (pinfunction "2_2") (pintype "passive"))
      (node (ref "R13") (pin "2") (pinfunction "2_2") (pintype "passive"))
      (node (ref "V5") (pin "1") (pinfunction "G_1") (pintype "passive"))
    )
    (net (code "41") (name "Net-(V6-D)") (class "Default")
      (node (ref "R14") (pin "1") (pinfunction "1_1") (pintype "passive"))
      (node (ref "V6") (pin "3") (pinfunction "D_3") (pintype "passive"))
    )
    (net (code "42") (name "Net-(V7-G)") (class "Default")
      (node (ref "C11") (pin "2") (pinfunction "2_2") (pintype "passive"))
      (node (ref "R16") (pin "2") (pinfunction "2_2") (pintype "passive"))
      (node (ref "V7") (pin "1") (pinfunction "G_1") (pintype "passive"))
    )
    (net (code "43") (name "Net-(V8-D)") (class "Default")
      (node (ref "R17") (pin "1") (pinfunction "1_1") (pintype "passive"))
      (node (ref "V8") (pin "3") (pinfunction "D_3") (pintype "passive"))
    )
    (net (code "44") (name "RELAY_1") (class "Default")
      (node (ref "C8") (pin "1") (pinfunction "1_1") (pintype "passive"))
      (node (ref "D3") (pin "14") (pinfunction "P7_14") (pintype "input"))
      (node (ref "R9") (pin "2") (pinfunction "2_2") (pintype "passive"))
      (node (ref "V2") (pin "1") (pinfunction "G_1") (pintype "passive"))
    )
    (net (code "45") (name "RELAY_2") (class "Default")
      (node (ref "C9") (pin "1") (pinfunction "1_1") (pintype "passive"))
      (node (ref "D3") (pin "13") (pinfunction "P6_13") (pintype "input"))
      (node (ref "R12") (pin "2") (pinfunction "2_2") (pintype "passive"))
      (node (ref "V4") (pin "1") (pinfunction "G_1") (pintype "passive"))
    )
    (net (code "46") (name "RELAY_3") (class "Default")
      (node (ref "C10") (pin "1") (pinfunction "1_1") (pintype "passive"))
      (node (ref "D3") (pin "12") (pinfunction "P5_12") (pintype "input"))
      (node (ref "R15") (pin "2") (pinfunction "2_2") (pintype "passive"))
      (node (ref "V6") (pin "1") (pinfunction "G_1") (pintype "passive"))
    )
    (net (code "47") (name "RELAY_4") (class "Default")
      (node (ref "C11") (pin "1") (pinfunction "1_1") (pintype "passive"))
      (node (ref "D3") (pin "11") (pinfunction "P4_11") (pintype "input"))
      (node (ref "R18") (pin "2") (pinfunction "2_2") (pintype "passive"))
      (node (ref "V8") (pin "1") (pinfunction "G_1") (pintype "passive"))
    )
    (net (code "48") (name "RESET_N") (class "Default")
      (node (ref "D3") (pin "15") (pinfunction "RESET_N_15") (pintype "bidirectional"))
      (node (ref "D4") (pin "1") (pinfunction "RESET_1") (pintype "bidirectional"))
      (node (ref "R6") (pin "1") (pinfunction "1_1") (pintype "passive"))
    )
    (net (code "49") (name "unconnected-(D1-OS-Pad3)") (class "Default")
      (node (ref "D1") (pin "3") (pinfunction "OS_3") (pintype "bidirectional"))
    )
    (net (code "50") (name "unconnected-(D2-WP-Pad7)") (class "Default")
      (node (ref "D2") (pin "7") (pinfunction "WP_7") (pintype "bidirectional"))
    )
  )
)
